# USBasp.net
KiCad netlist of a schematic drawn in Altium Designer
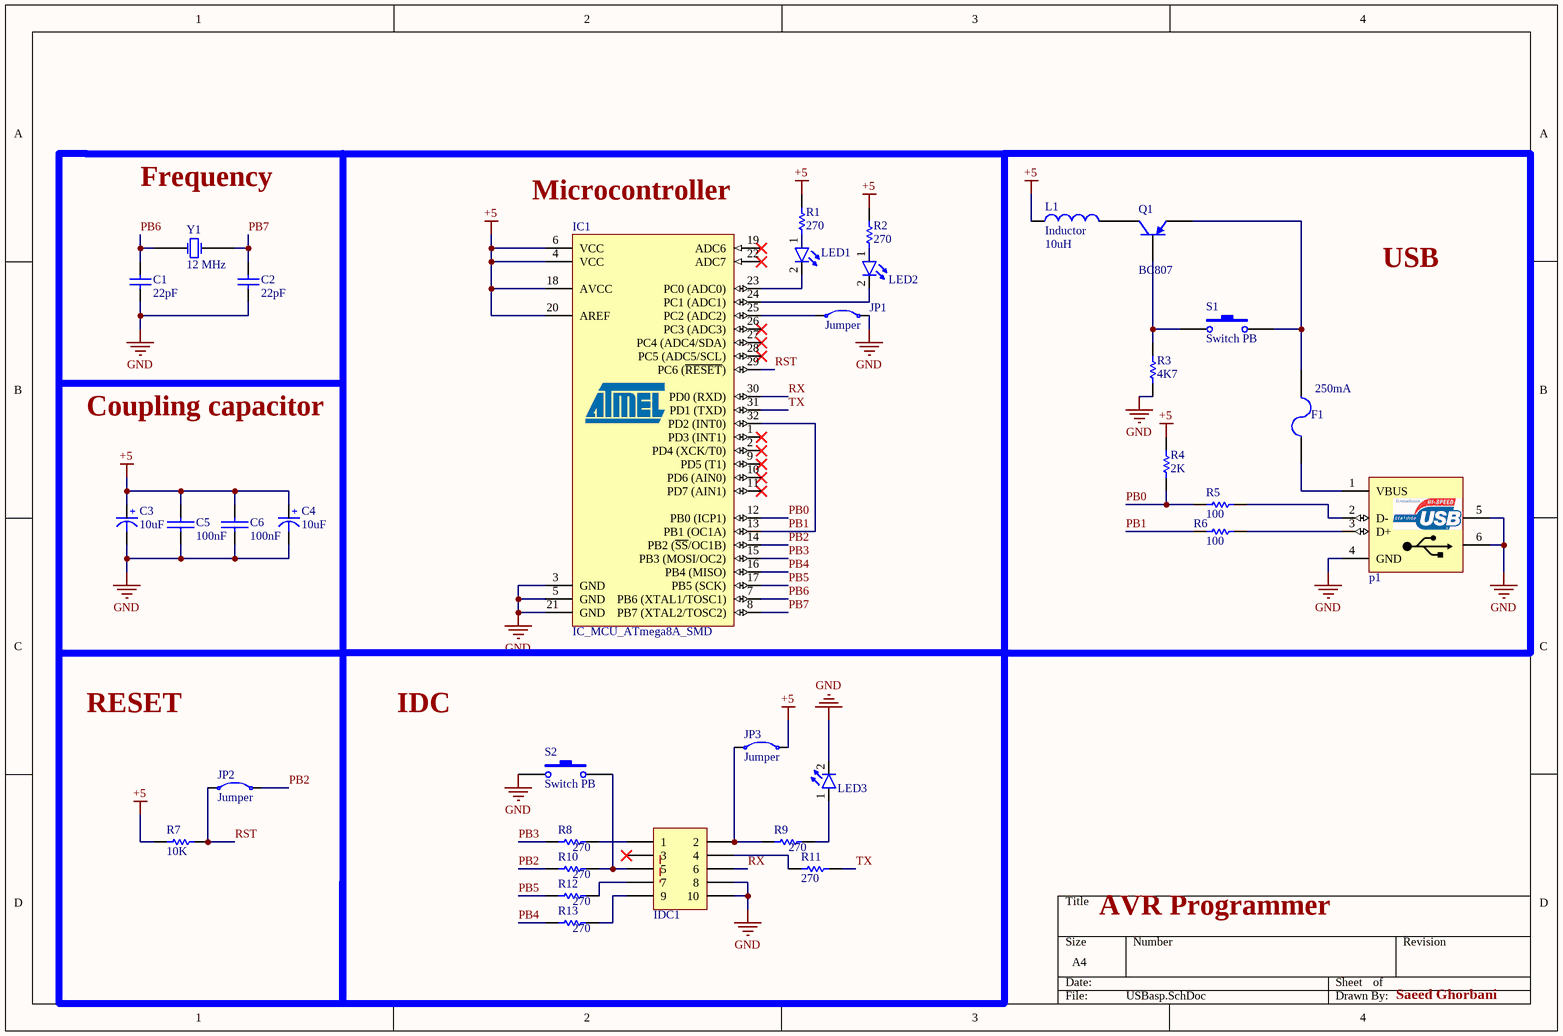
[diagram p0: USBasp.SchDoc]

(export (version "E")
  (design (tool "Eeschema 10.0.6"))
  (components
    (comp (ref "C1")
      (value "22pF")
      (footprint "CAPC3413X12N")
      (description "CAP 0805")
      (fields (field (name "DESIGNER") "Abbas Basereh"))
      (libsource (lib "General 1") (part "CAP SMD 0805"))
    )
    (comp (ref "C2")
      (value "22pF")
      (footprint "CAPC3413X12N")
      (description "CAP 0805")
      (fields (field (name "DESIGNER") "Abbas Basereh"))
      (libsource (lib "General 1") (part "CAP SMD 0805"))
    )
    (comp (ref "C3")
      (value "10uF")
      (footprint "CAPP 1206 (3216X18L) Size A")
      (description "Polar Capacitor")
      (fields (field (name "VOLTAGE") "16V") (field (name "DESIGNER") "Saeid Jorablo"))
      (libsource (lib "General 2") (part "Cap-Polar"))
    )
    (comp (ref "C4")
      (value "10uF")
      (footprint "CAPP 1206 (3216X18L) Size A")
      (description "Polar Capacitor")
      (fields (field (name "VOLTAGE") "16V") (field (name "DESIGNER") "Saeid Jorablo"))
      (libsource (lib "General 2") (part "Cap-Polar"))
    )
    (comp (ref "C5")
      (value "100nF")
      (footprint "SMD_CAP_0805")
      (description "Bipolar Capacitor")
      (fields (field (name "VOLTAGE") "100V") (field (name "DESIGNER") "Saeid Jorablo"))
      (libsource (lib "General 2") (part "Cap-Bipolar"))
    )
    (comp (ref "C6")
      (value "100nF")
      (footprint "SMD_CAP_0805")
      (description "Bipolar Capacitor")
      (fields (field (name "VOLTAGE") "100V") (field (name "DESIGNER") "Saeid Jorablo"))
      (libsource (lib "General 2") (part "Cap-Bipolar"))
    )
    (comp (ref "F1")
      (value "250mA")
      (footprint "1206 FUSE")
      (description "SMD Fuses 1206")
      (fields (field (name "DESIGNER") "Abbas Basereh"))
      (libsource (lib "General 1") (part "Fuse SMD1206"))
    )
    (comp (ref "IC1")
      (value "IC_MCU_ATmega8A_SMD")
      (footprint "32A_N")
      (fields
        (field (name "VOLTAGE") "(V)")
        (field (name "PUBLISHER") "Saeid UnLimited")
        (field (name "DESIGNER") "Eng. Saeid Jorablo")
      )
      (libsource (lib "General 3") (part "IC_MCU_ATmega8A_SMD"))
    )
    (comp (ref "IDC1")
      (value "CONNECTOR_IDC_5X2")
      (footprint "IDC2.54-10PIN - CROSS")
      (description "Header, 5-Pin, Dual row")
      (fields
        (field (name "MANUFACTURER") "CHINA")
        (field (name "PUBLISHER") "ABBAS BASEREH")
        (field (name "DESIGNER") "ABBAS BASEREH")
      )
      (libsource (lib "General 1") (part "IDC_5X2 HEADER"))
    )
    (comp (ref "JP1")
      (value "Jumper")
      (footprint "JP254_V")
      (description "Jumper Component")
      (fields (field (name "DESIGNER") "Eng. Saeid Jorablo") (field (name "PUBLISHER") "SJ Unlimited"))
      (libsource (lib "Passive Components") (part "JP"))
    )
    (comp (ref "JP2")
      (value "Jumper")
      (footprint "JP254_V")
      (description "Jumper Component")
      (fields (field (name "DESIGNER") "Eng. Saeid Jorablo") (field (name "PUBLISHER") "SJ Unlimited"))
      (libsource (lib "Passive Components") (part "JP"))
    )
    (comp (ref "JP3")
      (value "Jumper")
      (footprint "JP254_V")
      (description "Jumper Component")
      (fields (field (name "DESIGNER") "Eng. Saeid Jorablo") (field (name "PUBLISHER") "SJ Unlimited"))
      (libsource (lib "Passive Components") (part "JP"))
    )
    (comp (ref "L1")
      (value "Inductor")
      (footprint "INDC1608L")
      (fields (field (name "ALTIUM_VALUE") "10uH") (field (name "PUBLISHER") "Altium Limited"))
      (libsource (lib "General 2") (part "Inductor"))
    )
    (comp (ref "LED1")
      (value "1206")
      (footprint "LED SMD 1206")
      (description "LED")
      (fields (field (name "DESIGNER") "Saeid Jorablo"))
      (libsource (lib "General 2") (part "LED"))
    )
    (comp (ref "LED2")
      (value "Red")
      (footprint "LED SMD 1206")
      (description "LED")
      (fields (field (name "DESIGNER") "Saeid Jorablo"))
      (libsource (lib "General 2") (part "LED"))
    )
    (comp (ref "LED3")
      (value "Red")
      (footprint "LED SMD 1206")
      (description "LED")
      (fields (field (name "DESIGNER") "Saeid Jorablo"))
      (libsource (lib "General 2") (part "LED"))
    )
    (comp (ref "p1")
      (value "USB Connector")
      (footprint "USB A TYPE Right Angle")
      (description "USB Connector-A Type")
      (fields (field (name "DESIGNER") "ABBAS BASEREH") (field (name "PUBLISHER") "ABBAS BASEREH"))
      (libsource (lib "General 1") (part "USB A CONNECTOR"))
    )
    (comp (ref "Q1")
      (value "BC807")
      (footprint "SOT23_BEC_N")
      (description "PNP Bipolar Transistor")
      (fields (field (name "PUBLISHER") "Altium Limited"))
      (libsource (lib "General 2") (part "PNP"))
    )
    (comp (ref "R1")
      (value "270")
      (footprint "RESC3413X04N")
      (description "RES 0805")
      (fields (field (name "DESIGNER") "Abbas Basereh"))
      (libsource (lib "General 1") (part "RES 0805 0.125W"))
    )
    (comp (ref "R2")
      (value "270")
      (footprint "RESC3413X04N")
      (description "RES 0805")
      (fields (field (name "DESIGNER") "Abbas Basereh"))
      (libsource (lib "General 1") (part "RES 0805 0.125W"))
    )
    (comp (ref "R3")
      (value "4K7")
      (footprint "RESC3413X04N")
      (description "RES 0805")
      (fields (field (name "DESIGNER") "Abbas Basereh"))
      (libsource (lib "General 1") (part "RES 0805 0.125W"))
    )
    (comp (ref "R4")
      (value "2K")
      (footprint "RESC3413X04N")
      (description "RES 0805")
      (fields (field (name "DESIGNER") "Abbas Basereh"))
      (libsource (lib "General 1") (part "RES 0805 0.125W"))
    )
    (comp (ref "R5")
      (value "100")
      (footprint "RESC3413X04N")
      (description "RES 0805")
      (fields (field (name "DESIGNER") "Abbas Basereh"))
      (libsource (lib "General 1") (part "RES 0805 0.125W"))
    )
    (comp (ref "R6")
      (value "100")
      (footprint "RESC3413X04N")
      (description "RES 0805")
      (fields (field (name "DESIGNER") "Abbas Basereh"))
      (libsource (lib "General 1") (part "RES 0805 0.125W"))
    )
    (comp (ref "R7")
      (value "10K")
      (footprint "RESC3413X04N")
      (description "RES 0805")
      (fields (field (name "DESIGNER") "Abbas Basereh"))
      (libsource (lib "General 1") (part "RES 0805 0.125W"))
    )
    (comp (ref "R8")
      (value "270")
      (footprint "RESC3413X04N")
      (description "RES 0805")
      (fields (field (name "DESIGNER") "Abbas Basereh"))
      (libsource (lib "General 1") (part "RES 0805 0.125W"))
    )
    (comp (ref "R9")
      (value "270")
      (footprint "RESC3413X04N")
      (description "RES 0805")
      (fields (field (name "DESIGNER") "Abbas Basereh"))
      (libsource (lib "General 1") (part "RES 0805 0.125W"))
    )
    (comp (ref "R10")
      (value "270")
      (footprint "RESC3413X04N")
      (description "RES 0805")
      (fields (field (name "DESIGNER") "Abbas Basereh"))
      (libsource (lib "General 1") (part "RES 0805 0.125W"))
    )
    (comp (ref "R11")
      (value "270")
      (footprint "RESC3413X04N")
      (description "RES 0805")
      (fields (field (name "DESIGNER") "Abbas Basereh"))
      (libsource (lib "General 1") (part "RES 0805 0.125W"))
    )
    (comp (ref "R12")
      (value "270")
      (footprint "RESC3413X04N")
      (description "RES 0805")
      (fields (field (name "DESIGNER") "Abbas Basereh"))
      (libsource (lib "General 1") (part "RES 0805 0.125W"))
    )
    (comp (ref "R13")
      (value "270")
      (footprint "RESC3413X04N")
      (description "RES 0805")
      (fields (field (name "DESIGNER") "Abbas Basereh"))
      (libsource (lib "General 1") (part "RES 0805 0.125W"))
    )
    (comp (ref "S1")
      (value "Switch PB")
      (footprint "SW-PB")
      (description "Push Button Switch")
      (libsource (lib "General 2") (part "Switch PB"))
    )
    (comp (ref "S2")
      (value "Switch PB")
      (footprint "SW-PB")
      (description "Push Button Switch")
      (libsource (lib "General 2") (part "Switch PB"))
    )
    (comp (ref "Y1")
      (value "12 MHz")
      (footprint "Crystal SMD")
      (description "XTAL Crystal")
      (fields (field (name "DESIGNER") "ABBAS BASEREH"))
      (libsource (lib "General 1") (part "XTAL_Crystal"))
    )
  )
  (nets
    (net (code "1") (name "+5") (class "Default")
      (node (ref "C3") (pin "1") (pinfunction "+_1") (pintype "passive"))
      (node (ref "C4") (pin "1") (pinfunction "+_1") (pintype "passive"))
      (node (ref "C5") (pin "1") (pinfunction "+_1") (pintype "passive"))
      (node (ref "C6") (pin "1") (pinfunction "+_1") (pintype "passive"))
      (node (ref "IC1") (pin "18") (pinfunction "AVCC_18") (pintype "power_in"))
      (node (ref "IC1") (pin "20") (pinfunction "AREF_20") (pintype "power_in"))
      (node (ref "IC1") (pin "4") (pinfunction "VCC_4") (pintype "power_in"))
      (node (ref "IC1") (pin "6") (pinfunction "VCC_6") (pintype "power_in"))
      (node (ref "JP3") (pin "2") (pinfunction "2_2") (pintype "passive"))
      (node (ref "L1") (pin "1") (pinfunction "1_1") (pintype "passive"))
      (node (ref "R1") (pin "2") (pinfunction "2_2") (pintype "passive"))
      (node (ref "R2") (pin "2") (pinfunction "2_2") (pintype "passive"))
      (node (ref "R4") (pin "2") (pinfunction "2_2") (pintype "passive"))
      (node (ref "R7") (pin "1") (pinfunction "1_1") (pintype "passive"))
    )
    (net (code "2") (name "/PB0") (class "Default")
      (node (ref "IC1") (pin "12") (pinfunction "PB0_(ICP1)_12") (pintype "bidirectional"))
      (node (ref "R4") (pin "1") (pinfunction "1_1") (pintype "passive"))
      (node (ref "R5") (pin "1") (pinfunction "1_1") (pintype "passive"))
    )
    (net (code "3") (name "/PB1") (class "Default")
      (node (ref "IC1") (pin "13") (pinfunction "PB1_(OC1A)_13") (pintype "bidirectional"))
      (node (ref "IC1") (pin "32") (pinfunction "PD2_(INT0)_32") (pintype "bidirectional"))
      (node (ref "R6") (pin "1") (pinfunction "1_1") (pintype "passive"))
    )
    (net (code "4") (name "/PB2") (class "Default")
      (node (ref "IC1") (pin "14") (pinfunction "PB2_(~{SS}/OC1B)_14") (pintype "bidirectional"))
      (node (ref "JP2") (pin "2") (pinfunction "2_2") (pintype "passive"))
      (node (ref "R10") (pin "1") (pinfunction "1_1") (pintype "passive"))
    )
    (net (code "5") (name "/PB3") (class "Default")
      (node (ref "IC1") (pin "15") (pinfunction "PB3_(MOSI/OC2)_15") (pintype "bidirectional"))
      (node (ref "R8") (pin "1") (pinfunction "1_1") (pintype "passive"))
    )
    (net (code "6") (name "/PB4") (class "Default")
      (node (ref "IC1") (pin "16") (pinfunction "PB4_(MISO)_16") (pintype "bidirectional"))
      (node (ref "R13") (pin "1") (pinfunction "1_1") (pintype "passive"))
    )
    (net (code "7") (name "/PB5") (class "Default")
      (node (ref "IC1") (pin "17") (pinfunction "PB5_(SCK)_17") (pintype "bidirectional"))
      (node (ref "R12") (pin "1") (pinfunction "1_1") (pintype "passive"))
    )
    (net (code "8") (name "/PB6") (class "Default")
      (node (ref "C1") (pin "2") (pinfunction "2_2") (pintype "passive"))
      (node (ref "IC1") (pin "7") (pinfunction "PB6_(XTAL1/TOSC1)_7") (pintype "bidirectional"))
      (node (ref "Y1") (pin "1") (pinfunction "OSC1_1") (pintype "passive"))
    )
    (net (code "9") (name "/PB7") (class "Default")
      (node (ref "C2") (pin "2") (pinfunction "2_2") (pintype "passive"))
      (node (ref "IC1") (pin "8") (pinfunction "PB7_(XTAL2/TOSC2)_8") (pintype "bidirectional"))
      (node (ref "Y1") (pin "2") (pinfunction "OSC2_2") (pintype "passive"))
    )
    (net (code "10") (name "/RST") (class "Default")
      (node (ref "IC1") (pin "29") (pinfunction "PC6_(~{RESET})_29") (pintype "bidirectional"))
      (node (ref "JP2") (pin "1") (pinfunction "1_1") (pintype "passive"))
      (node (ref "R7") (pin "2") (pinfunction "2_2") (pintype "passive"))
    )
    (net (code "11") (name "/RX") (class "Default")
      (node (ref "IC1") (pin "30") (pinfunction "PD0_(RXD)_30") (pintype "bidirectional"))
      (node (ref "IDC1") (pin "6") (pinfunction "6_6") (pintype "passive"))
    )
    (net (code "12") (name "/TX") (class "Default")
      (node (ref "IC1") (pin "31") (pinfunction "PD1_(TXD)_31") (pintype "bidirectional"))
      (node (ref "R11") (pin "2") (pinfunction "2_2") (pintype "passive"))
    )
    (net (code "13") (name "GND") (class "Default")
      (node (ref "C1") (pin "1") (pinfunction "1_1") (pintype "passive"))
      (node (ref "C2") (pin "1") (pinfunction "1_1") (pintype "passive"))
      (node (ref "C3") (pin "2") (pinfunction "-_2") (pintype "passive"))
      (node (ref "C4") (pin "2") (pinfunction "-_2") (pintype "passive"))
      (node (ref "C5") (pin "2") (pinfunction "-_2") (pintype "passive"))
      (node (ref "C6") (pin "2") (pinfunction "-_2") (pintype "passive"))
      (node (ref "IC1") (pin "21") (pinfunction "GND_21") (pintype "power_in"))
      (node (ref "IC1") (pin "3") (pinfunction "GND_3") (pintype "power_in"))
      (node (ref "IC1") (pin "5") (pinfunction "GND_5") (pintype "power_in"))
      (node (ref "IDC1") (pin "10") (pinfunction "10_10") (pintype "passive"))
      (node (ref "IDC1") (pin "8") (pinfunction "8_8") (pintype "passive"))
      (node (ref "JP1") (pin "2") (pinfunction "2_2") (pintype "passive"))
      (node (ref "LED3") (pin "2") (pinfunction "K_2") (pintype "passive"))
      (node (ref "R3") (pin "1") (pinfunction "1_1") (pintype "passive"))
      (node (ref "S2") (pin "1") (pinfunction "1_1") (pintype "passive"))
      (node (ref "p1") (pin "4") (pinfunction "GND_4") (pintype "power_in"))
      (node (ref "p1") (pin "5") (pinfunction "MH_5") (pintype "power_in"))
      (node (ref "p1") (pin "6") (pinfunction "MH_6") (pintype "power_in"))
    )
    (net (code "14") (name "Net-(IC1-PC0_(ADC0))") (class "Default")
      (node (ref "IC1") (pin "23") (pinfunction "PC0_(ADC0)_23") (pintype "bidirectional"))
      (node (ref "LED1") (pin "2") (pinfunction "K_2") (pintype "passive"))
    )
    (net (code "15") (name "Net-(IC1-PC1_(ADC1))") (class "Default")
      (node (ref "IC1") (pin "24") (pinfunction "PC1_(ADC1)_24") (pintype "bidirectional"))
      (node (ref "LED2") (pin "2") (pinfunction "K_2") (pintype "passive"))
    )
    (net (code "16") (name "Net-(IC1-PC2_(ADC2))") (class "Default")
      (node (ref "IC1") (pin "25") (pinfunction "PC2_(ADC2)_25") (pintype "bidirectional"))
      (node (ref "JP1") (pin "1") (pinfunction "1_1") (pintype "passive"))
    )
    (net (code "17") (name "Net-(IDC1-Pad1)") (class "Default")
      (node (ref "IDC1") (pin "1") (pinfunction "1_1") (pintype "passive"))
      (node (ref "R8") (pin "2") (pinfunction "2_2") (pintype "passive"))
    )
    (net (code "18") (name "Net-(IDC1-Pad2)") (class "Default")
      (node (ref "IDC1") (pin "2") (pinfunction "2_2") (pintype "passive"))
      (node (ref "JP3") (pin "1") (pinfunction "1_1") (pintype "passive"))
      (node (ref "R9") (pin "1") (pinfunction "1_1") (pintype "passive"))
    )
    (net (code "19") (name "Net-(IDC1-Pad4)") (class "Default")
      (node (ref "IDC1") (pin "4") (pinfunction "4_4") (pintype "passive"))
      (node (ref "R11") (pin "1") (pinfunction "1_1") (pintype "passive"))
    )
    (net (code "20") (name "Net-(IDC1-Pad5)") (class "Default")
      (node (ref "IDC1") (pin "5") (pinfunction "5_5") (pintype "passive"))
      (node (ref "R10") (pin "2") (pinfunction "2_2") (pintype "passive"))
      (node (ref "S2") (pin "2") (pinfunction "2_2") (pintype "passive"))
    )
    (net (code "21") (name "Net-(IDC1-Pad7)") (class "Default")
      (node (ref "IDC1") (pin "7") (pinfunction "7_7") (pintype "passive"))
      (node (ref "R12") (pin "2") (pinfunction "2_2") (pintype "passive"))
    )
    (net (code "22") (name "Net-(IDC1-Pad9)") (class "Default")
      (node (ref "IDC1") (pin "9") (pinfunction "9_9") (pintype "passive"))
      (node (ref "R13") (pin "2") (pinfunction "2_2") (pintype "passive"))
    )
    (net (code "23") (name "Net-(LED1-A)") (class "Default")
      (node (ref "LED1") (pin "1") (pinfunction "A_1") (pintype "passive"))
      (node (ref "R1") (pin "1") (pinfunction "1_1") (pintype "passive"))
    )
    (net (code "24") (name "Net-(LED2-A)") (class "Default")
      (node (ref "LED2") (pin "1") (pinfunction "A_1") (pintype "passive"))
      (node (ref "R2") (pin "1") (pinfunction "1_1") (pintype "passive"))
    )
    (net (code "25") (name "Net-(LED3-A)") (class "Default")
      (node (ref "LED3") (pin "1") (pinfunction "A_1") (pintype "passive"))
      (node (ref "R9") (pin "2") (pinfunction "2_2") (pintype "passive"))
    )
    (net (code "26") (name "Net-(Q1-B)") (class "Default")
      (node (ref "Q1") (pin "1") (pinfunction "B_1") (pintype "passive"))
      (node (ref "R3") (pin "2") (pinfunction "2_2") (pintype "passive"))
      (node (ref "S1") (pin "1") (pinfunction "1_1") (pintype "passive"))
    )
    (net (code "27") (name "Net-(Q1-C)") (class "Default")
      (node (ref "L1") (pin "2") (pinfunction "2_2") (pintype "passive"))
      (node (ref "Q1") (pin "3") (pinfunction "C_3") (pintype "passive"))
    )
    (net (code "28") (name "Net-(Q1-E)") (class "Default")
      (node (ref "F1") (pin "2") (pinfunction "2_2") (pintype "passive"))
      (node (ref "Q1") (pin "2") (pinfunction "E_2") (pintype "passive"))
      (node (ref "S1") (pin "2") (pinfunction "2_2") (pintype "passive"))
    )
    (net (code "29") (name "Net-(p1-D+)") (class "Default")
      (node (ref "R6") (pin "2") (pinfunction "2_2") (pintype "passive"))
      (node (ref "p1") (pin "3") (pinfunction "D+_3") (pintype "bidirectional"))
    )
    (net (code "30") (name "Net-(p1-D-)") (class "Default")
      (node (ref "R5") (pin "2") (pinfunction "2_2") (pintype "passive"))
      (node (ref "p1") (pin "2") (pinfunction "D-_2") (pintype "bidirectional"))
    )
    (net (code "31") (name "Net-(p1-VBUS)") (class "Default")
      (node (ref "F1") (pin "1") (pinfunction "1_1") (pintype "passive"))
      (node (ref "p1") (pin "1") (pinfunction "VBUS_1") (pintype "power_in"))
    )
    (net (code "32") (name "unconnected-(IC1-ADC6-Pad19)") (class "Default")
      (node (ref "IC1") (pin "19") (pinfunction "ADC6_19") (pintype "input+no_connect"))
    )
    (net (code "33") (name "unconnected-(IC1-ADC7-Pad22)") (class "Default")
      (node (ref "IC1") (pin "22") (pinfunction "ADC7_22") (pintype "input+no_connect"))
    )
    (net (code "34") (name "unconnected-(IC1-PC3_(ADC3)-Pad26)") (class "Default")
      (node (ref "IC1") (pin "26") (pinfunction "PC3_(ADC3)_26") (pintype "bidirectional+no_connect"))
    )
    (net (code "35") (name "unconnected-(IC1-PC4_(ADC4{slash}SDA)-Pad27)") (class "Default")
      (node (ref "IC1") (pin "27") (pinfunction "PC4_(ADC4/SDA)_27") (pintype "bidirectional+no_connect"))
    )
    (net (code "36") (name "unconnected-(IC1-PC5_(ADC5{slash}SCL)-Pad28)") (class "Default")
      (node (ref "IC1") (pin "28") (pinfunction "PC5_(ADC5/SCL)_28") (pintype "bidirectional+no_connect"))
    )
    (net (code "37") (name "unconnected-(IC1-PD3_(INT1)-Pad1)") (class "Default")
      (node (ref "IC1") (pin "1") (pinfunction "PD3_(INT1)_1") (pintype "bidirectional+no_connect"))
    )
    (net (code "38") (name "unconnected-(IC1-PD4_(XCK{slash}T0)-Pad2)") (class "Default")
      (node (ref "IC1") (pin "2") (pinfunction "PD4_(XCK/T0)_2") (pintype "bidirectional+no_connect"))
    )
    (net (code "39") (name "unconnected-(IC1-PD5_(T1)-Pad9)") (class "Default")
      (node (ref "IC1") (pin "9") (pinfunction "PD5_(T1)_9") (pintype "bidirectional+no_connect"))
    )
    (net (code "40") (name "unconnected-(IC1-PD6_(AIN0)-Pad10)") (class "Default")
      (node (ref "IC1") (pin "10") (pinfunction "PD6_(AIN0)_10") (pintype "bidirectional+no_connect"))
    )
    (net (code "41") (name "unconnected-(IC1-PD7_(AIN1)-Pad11)") (class "Default")
      (node (ref "IC1") (pin "11") (pinfunction "PD7_(AIN1)_11") (pintype "bidirectional+no_connect"))
    )
    (net (code "42") (name "unconnected-(IDC1-Pad3)") (class "Default")
      (node (ref "IDC1") (pin "3") (pinfunction "3_3") (pintype "passive+no_connect"))
    )
  )
)
